# AirPi1-4.net
KiCad netlist of a schematic drawn in EAGLE
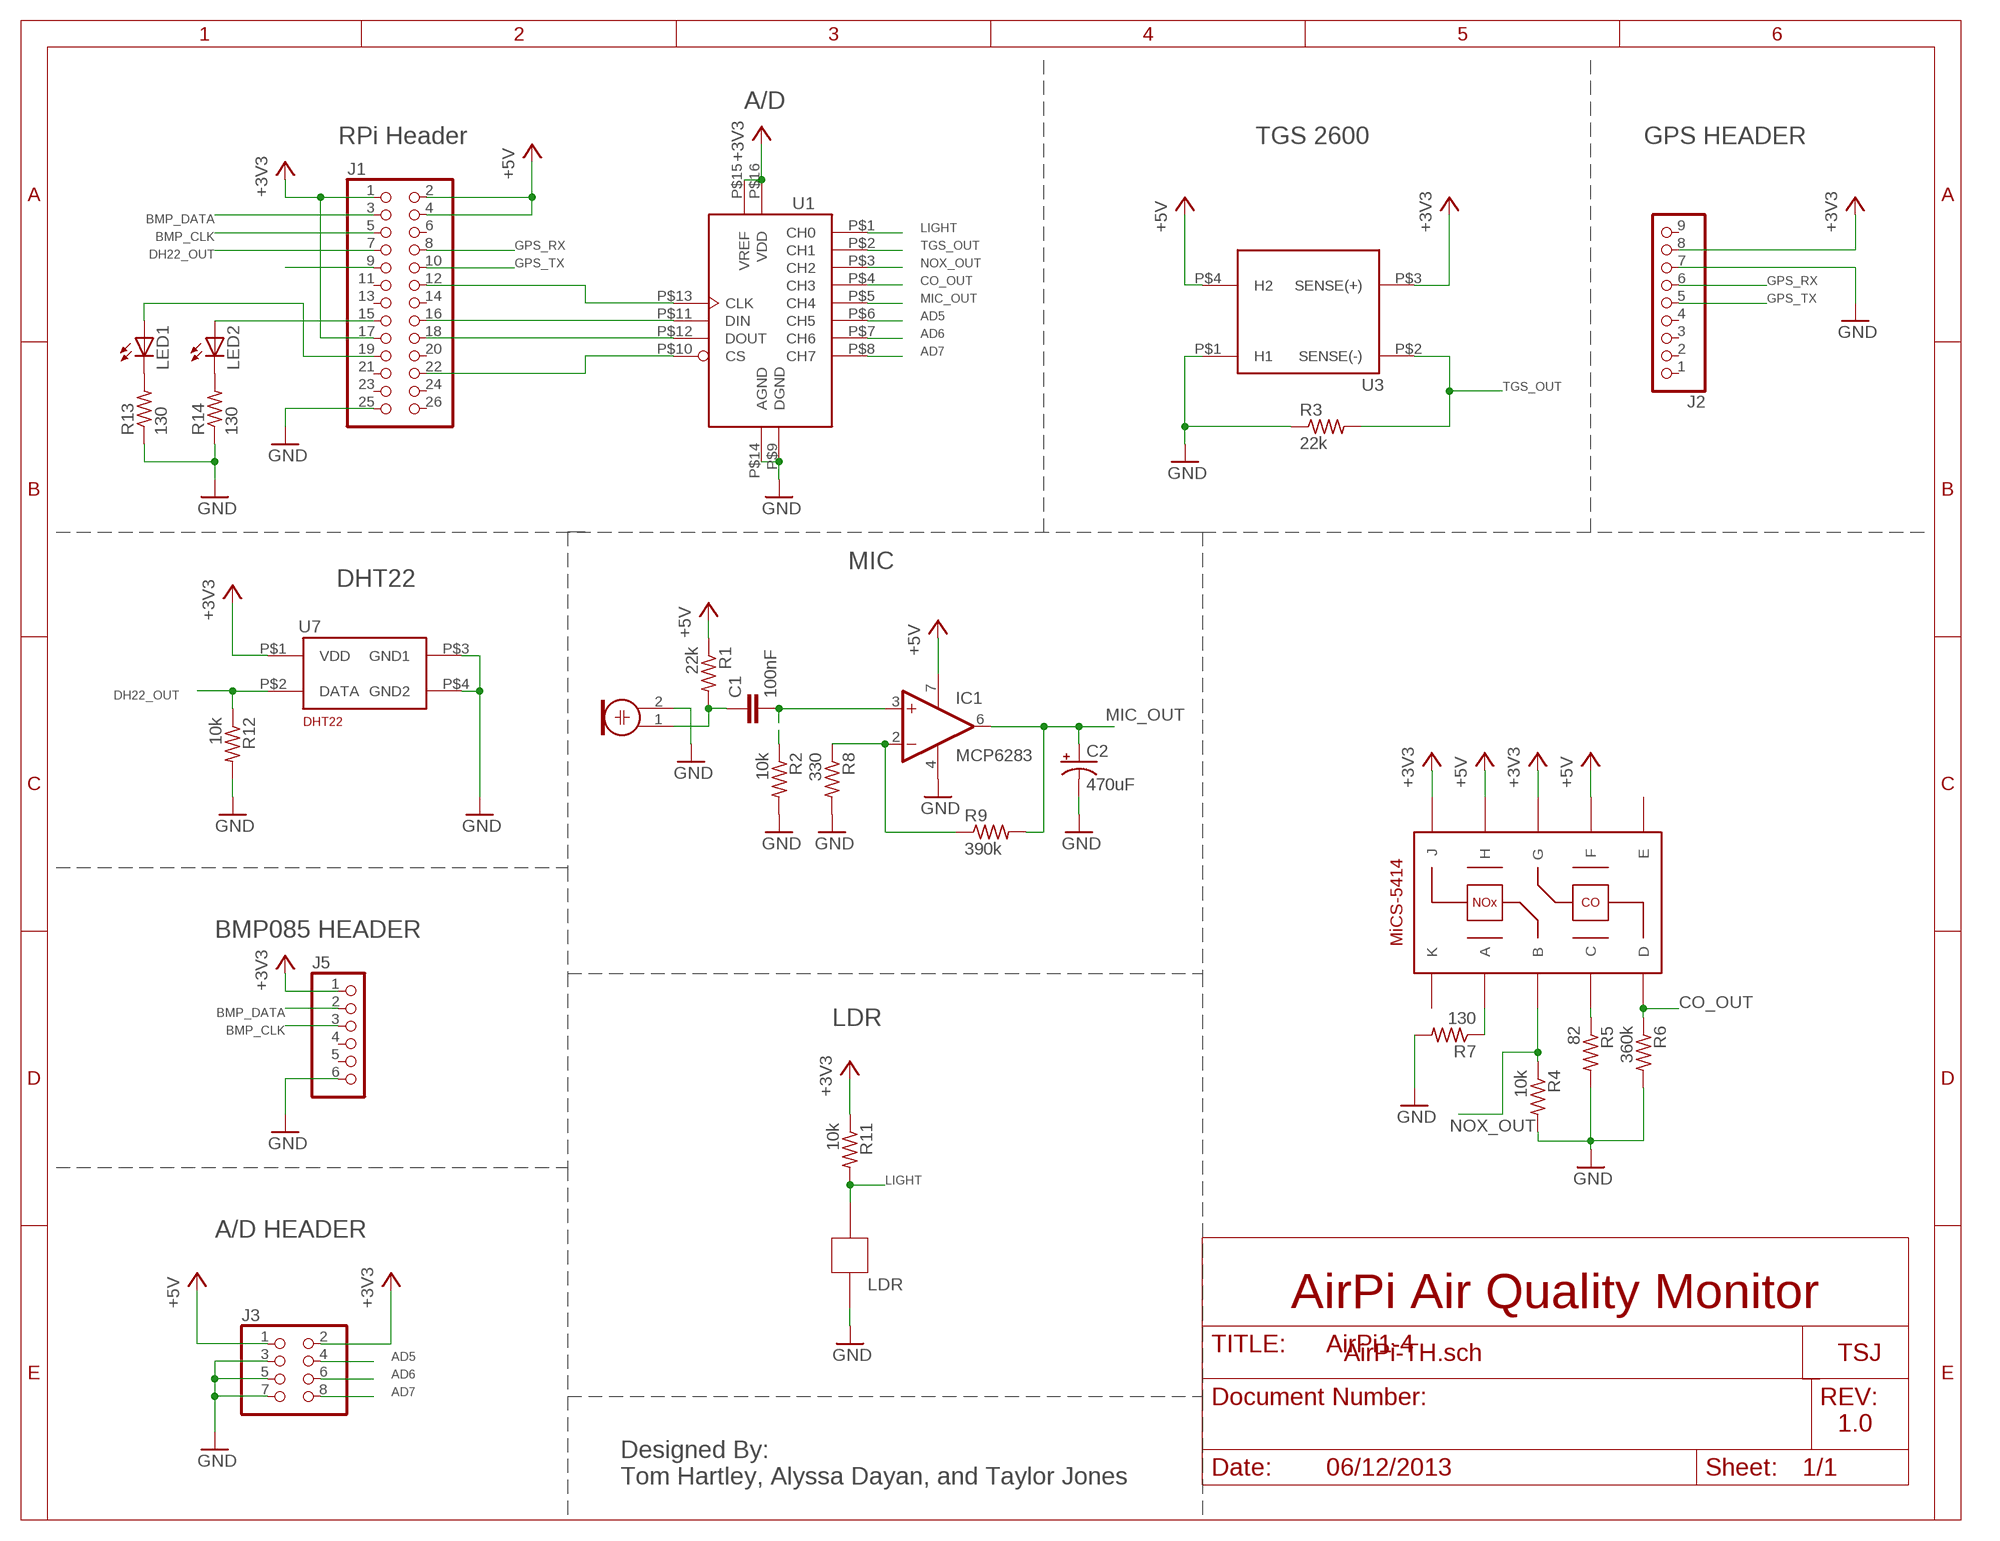
[diagram p0: schematic, sheet 1]

(export (version "E")
  (design (tool "Eeschema 10.0.6"))
  (components
    (comp (ref "C1")
      (value "100nF")
      (footprint "eagle-import:C2.5-4")
      (libsource (lib "eagle-import") (part "C2.5/4"))
    )
    (comp (ref "C2")
      (value "470uF")
      (footprint "eagle-import:E3,5-8")
      (libsource (lib "eagle-import") (part "CPOL-USE3.5-8"))
    )
    (comp (ref "IC1")
      (value "MCP6283")
      (footprint "eagle-import:DIL08")
      (libsource (lib "eagle-import") (part "OPAP344"))
    )
    (comp (ref "IC2")
      (value "MCP3008")
      (footprint "eagle-import:DIL16")
      (libsource (lib "eagle-import") (part "MCP30081"))
    )
    (comp (ref "J1")
      (value "PINHD-2X13")
      (footprint "eagle-import:2X13")
      (libsource (lib "eagle-import") (part "PINHD-2X13"))
    )
    (comp (ref "J2")
      (value "PINHD-1X9")
      (footprint "eagle-import:1X09-BIG")
      (libsource (lib "eagle-import") (part "PINHD-1X9"))
    )
    (comp (ref "J3")
      (value "PINHD-2X4")
      (footprint "eagle-import:2X04")
      (libsource (lib "eagle-import") (part "PINHD-2X4"))
    )
    (comp (ref "J5")
      (value "PINHD-1X6")
      (footprint "eagle-import:1X06")
      (libsource (lib "eagle-import") (part "PINHD-1X6"))
    )
    (comp (ref "LDR1")
      (value "LDR")
      (footprint "eagle-import:LED5MM")
      (libsource (lib "eagle-import") (part "LDR"))
    )
    (comp (ref "LED1")
      (value "LED3MM")
      (footprint "eagle-import:LED3MM")
      (libsource (lib "eagle-import") (part "LED3MM"))
    )
    (comp (ref "LED2")
      (value "LED3MM")
      (footprint "eagle-import:LED3MM")
      (libsource (lib "eagle-import") (part "LED3MM"))
    )
    (comp (ref "M1")
      (value "MIC")
      (footprint "eagle-import:WM-62PC_62PK")
      (libsource (lib "eagle-import") (part "ELECTRET_MICROPHON-WM-62PC/62PK"))
    )
    (comp (ref "MICS")
      (value "MICS-4514")
      (footprint "eagle-import:MICS-4514")
      (libsource (lib "eagle-import") (part "MICS-4514"))
    )
    (comp (ref "R1")
      (value "22k")
      (footprint "eagle-import:0207_10")
      (libsource (lib "eagle-import") (part "R-US_0207/10"))
    )
    (comp (ref "R2")
      (value "10k")
      (footprint "eagle-import:0207_10")
      (libsource (lib "eagle-import") (part "R-US_0207/10"))
    )
    (comp (ref "R3")
      (value "22k")
      (footprint "eagle-import:0207_10")
      (libsource (lib "eagle-import") (part "R-US_0207/10"))
    )
    (comp (ref "R4")
      (value "10k")
      (footprint "eagle-import:0207_10")
      (libsource (lib "eagle-import") (part "R-US_0207/10"))
    )
    (comp (ref "R5")
      (value "82")
      (footprint "eagle-import:0207_10")
      (libsource (lib "eagle-import") (part "R-US_0207/10"))
    )
    (comp (ref "R6")
      (value "360k")
      (footprint "eagle-import:0207_10")
      (libsource (lib "eagle-import") (part "R-US_0207/10"))
    )
    (comp (ref "R7")
      (value "130")
      (footprint "eagle-import:0207_10")
      (libsource (lib "eagle-import") (part "R-US_0207/10"))
    )
    (comp (ref "R8")
      (value "330")
      (footprint "eagle-import:0207_10")
      (libsource (lib "eagle-import") (part "R-US_0207/10"))
    )
    (comp (ref "R9")
      (value "390k")
      (footprint "eagle-import:0207_10")
      (libsource (lib "eagle-import") (part "R-US_0207/10"))
    )
    (comp (ref "R11")
      (value "10k")
      (footprint "eagle-import:0207_10")
      (libsource (lib "eagle-import") (part "R-US_0207/10"))
    )
    (comp (ref "R12")
      (value "10k")
      (footprint "eagle-import:0207_10")
      (libsource (lib "eagle-import") (part "R-US_0207/10"))
    )
    (comp (ref "R13")
      (value "130")
      (footprint "eagle-import:0207_10")
      (libsource (lib "eagle-import") (part "R-US_0207/10"))
    )
    (comp (ref "R14")
      (value "130")
      (footprint "eagle-import:0207_10")
      (libsource (lib "eagle-import") (part "R-US_0207/10"))
    )
    (comp (ref "U3")
      (value "TGS2600")
      (footprint "eagle-import:TGS2600")
      (libsource (lib "eagle-import") (part "TGS2600"))
    )
    (comp (ref "U7")
      (value "DHT22")
      (footprint "eagle-import:DHT22")
      (libsource (lib "eagle-import") (part "DHT22"))
    )
  )
  (nets
    (net (code "1") (name "+3V3") (class "Default")
      (node (ref "IC2") (pin "P$15") (pinfunction "VREF_P$15") (pintype "power_in"))
      (node (ref "IC2") (pin "P$16") (pinfunction "VDD_P$16") (pintype "power_in"))
      (node (ref "J1") (pin "1") (pinfunction "1_1") (pintype "passive"))
      (node (ref "J1") (pin "17") (pinfunction "17_17") (pintype "passive"))
      (node (ref "J2") (pin "8") (pinfunction "8_8") (pintype "passive"))
      (node (ref "J3") (pin "2") (pinfunction "2_2") (pintype "passive"))
      (node (ref "J5") (pin "1") (pinfunction "1_1") (pintype "passive"))
      (node (ref "MICS") (pin "G") (pinfunction "G_G") (pintype "bidirectional"))
      (node (ref "MICS") (pin "J") (pinfunction "J_J") (pintype "bidirectional"))
      (node (ref "R11") (pin "1") (pinfunction "1_1") (pintype "passive"))
      (node (ref "U3") (pin "P$3") (pinfunction "SENSE(+)_P$3") (pintype "bidirectional"))
      (node (ref "U7") (pin "P$1") (pinfunction "VDD_P$1") (pintype "power_in"))
    )
    (net (code "2") (name "+5V") (class "Default")
      (node (ref "IC1") (pin "7") (pinfunction "V+_7") (pintype "power_in"))
      (node (ref "J1") (pin "2") (pinfunction "2_2") (pintype "passive"))
      (node (ref "J1") (pin "4") (pinfunction "4_4") (pintype "passive"))
      (node (ref "J3") (pin "1") (pinfunction "1_1") (pintype "passive"))
      (node (ref "MICS") (pin "F") (pinfunction "F_F") (pintype "bidirectional"))
      (node (ref "MICS") (pin "H") (pinfunction "H_H") (pintype "bidirectional"))
      (node (ref "R1") (pin "1") (pinfunction "1_1") (pintype "passive"))
      (node (ref "U3") (pin "P$4") (pinfunction "H2_P$4") (pintype "power_in"))
    )
    (net (code "3") (name "/AD5") (class "Default")
      (node (ref "IC2") (pin "P$6") (pinfunction "CH5_P$6") (pintype "input"))
      (node (ref "J3") (pin "4") (pinfunction "4_4") (pintype "passive"))
    )
    (net (code "4") (name "/AD6") (class "Default")
      (node (ref "IC2") (pin "P$7") (pinfunction "CH6_P$7") (pintype "input"))
      (node (ref "J3") (pin "6") (pinfunction "6_6") (pintype "passive"))
    )
    (net (code "5") (name "/AD7") (class "Default")
      (node (ref "IC2") (pin "P$8") (pinfunction "CH7_P$8") (pintype "input"))
      (node (ref "J3") (pin "8") (pinfunction "8_8") (pintype "passive"))
    )
    (net (code "6") (name "/BMP_CLK") (class "Default")
      (node (ref "J1") (pin "5") (pinfunction "5_5") (pintype "passive"))
      (node (ref "J5") (pin "3") (pinfunction "3_3") (pintype "passive"))
    )
    (net (code "7") (name "/BMP_DATA") (class "Default")
      (node (ref "J1") (pin "3") (pinfunction "3_3") (pintype "passive"))
      (node (ref "J5") (pin "2") (pinfunction "2_2") (pintype "passive"))
    )
    (net (code "8") (name "/CO_OUT") (class "Default")
      (node (ref "IC2") (pin "P$4") (pinfunction "CH3_P$4") (pintype "input"))
      (node (ref "MICS") (pin "D") (pinfunction "D_D") (pintype "bidirectional"))
      (node (ref "R6") (pin "1") (pinfunction "1_1") (pintype "passive"))
    )
    (net (code "9") (name "/DH22_OUT") (class "Default")
      (node (ref "J1") (pin "7") (pinfunction "7_7") (pintype "passive"))
      (node (ref "R12") (pin "1") (pinfunction "1_1") (pintype "passive"))
      (node (ref "U7") (pin "P$2") (pinfunction "DATA_P$2") (pintype "bidirectional"))
    )
    (net (code "10") (name "/GPS_RX") (class "Default")
      (node (ref "J1") (pin "8") (pinfunction "8_8") (pintype "passive"))
      (node (ref "J2") (pin "6") (pinfunction "6_6") (pintype "passive"))
    )
    (net (code "11") (name "/GPS_TX") (class "Default")
      (node (ref "J1") (pin "10") (pinfunction "10_10") (pintype "passive"))
      (node (ref "J2") (pin "5") (pinfunction "5_5") (pintype "passive"))
    )
    (net (code "12") (name "/LIGHT") (class "Default")
      (node (ref "IC2") (pin "P$1") (pinfunction "CH0_P$1") (pintype "input"))
      (node (ref "LDR1") (pin "A") (pinfunction "P$1_A") (pintype "bidirectional"))
      (node (ref "R11") (pin "2") (pinfunction "2_2") (pintype "passive"))
    )
    (net (code "13") (name "/MIC_OUT") (class "Default")
      (node (ref "C2") (pin "+") (pinfunction "+_+") (pintype "passive"))
      (node (ref "IC1") (pin "6") (pinfunction "OUT_6") (pintype "output"))
      (node (ref "IC2") (pin "P$5") (pinfunction "CH4_P$5") (pintype "input"))
      (node (ref "R9") (pin "2") (pinfunction "2_2") (pintype "passive"))
    )
    (net (code "14") (name "/NOX_OUT") (class "Default")
      (node (ref "IC2") (pin "P$3") (pinfunction "CH2_P$3") (pintype "input"))
      (node (ref "MICS") (pin "B") (pinfunction "B_B") (pintype "bidirectional"))
      (node (ref "R4") (pin "1") (pinfunction "1_1") (pintype "passive"))
    )
    (net (code "15") (name "/TGS_OUT") (class "Default")
      (node (ref "IC2") (pin "P$2") (pinfunction "CH1_P$2") (pintype "input"))
      (node (ref "R3") (pin "2") (pinfunction "2_2") (pintype "passive"))
      (node (ref "U3") (pin "P$2") (pinfunction "SENSE(-)_P$2") (pintype "bidirectional"))
    )
    (net (code "16") (name "GND") (class "Default")
      (node (ref "C2") (pin "-") (pinfunction "-_-") (pintype "passive"))
      (node (ref "IC1") (pin "4") (pinfunction "V-_4") (pintype "power_in"))
      (node (ref "IC2") (pin "P$14") (pinfunction "AGND_P$14") (pintype "power_in"))
      (node (ref "IC2") (pin "P$9") (pinfunction "DGND_P$9") (pintype "power_in"))
      (node (ref "J1") (pin "25") (pinfunction "25_25") (pintype "passive"))
      (node (ref "J2") (pin "7") (pinfunction "7_7") (pintype "passive"))
      (node (ref "J3") (pin "3") (pinfunction "3_3") (pintype "passive"))
      (node (ref "J3") (pin "5") (pinfunction "5_5") (pintype "passive"))
      (node (ref "J3") (pin "7") (pinfunction "7_7") (pintype "passive"))
      (node (ref "J5") (pin "6") (pinfunction "6_6") (pintype "passive"))
      (node (ref "LDR1") (pin "K") (pinfunction "P$2_K") (pintype "bidirectional"))
      (node (ref "M1") (pin "2") (pinfunction "2_2") (pintype "passive"))
      (node (ref "R12") (pin "2") (pinfunction "2_2") (pintype "passive"))
      (node (ref "R13") (pin "1") (pinfunction "1_1") (pintype "passive"))
      (node (ref "R14") (pin "1") (pinfunction "1_1") (pintype "passive"))
      (node (ref "R2") (pin "2") (pinfunction "2_2") (pintype "passive"))
      (node (ref "R3") (pin "1") (pinfunction "1_1") (pintype "passive"))
      (node (ref "R4") (pin "2") (pinfunction "2_2") (pintype "passive"))
      (node (ref "R5") (pin "2") (pinfunction "2_2") (pintype "passive"))
      (node (ref "R6") (pin "2") (pinfunction "2_2") (pintype "passive"))
      (node (ref "R7") (pin "2") (pinfunction "2_2") (pintype "passive"))
      (node (ref "R8") (pin "2") (pinfunction "2_2") (pintype "passive"))
      (node (ref "U3") (pin "P$1") (pinfunction "H1_P$1") (pintype "power_in"))
      (node (ref "U7") (pin "P$3") (pinfunction "GND1_P$3") (pintype "power_in"))
      (node (ref "U7") (pin "P$4") (pinfunction "GND2_P$4") (pintype "bidirectional"))
    )
    (net (code "17") (name "Net-(C1-Pad1)") (class "Default")
      (node (ref "C1") (pin "1") (pinfunction "1_1") (pintype "passive"))
      (node (ref "M1") (pin "1") (pinfunction "1_1") (pintype "passive"))
      (node (ref "R1") (pin "2") (pinfunction "2_2") (pintype "passive"))
    )
    (net (code "18") (name "Net-(IC1-+IN)") (class "Default")
      (node (ref "C1") (pin "2") (pinfunction "2_2") (pintype "passive"))
      (node (ref "IC1") (pin "3") (pinfunction "+IN_3") (pintype "input"))
      (node (ref "R2") (pin "1") (pinfunction "1_1") (pintype "passive"))
    )
    (net (code "19") (name "Net-(IC1--IN)") (class "Default")
      (node (ref "IC1") (pin "2") (pinfunction "-IN_2") (pintype "input"))
      (node (ref "R8") (pin "1") (pinfunction "1_1") (pintype "passive"))
      (node (ref "R9") (pin "1") (pinfunction "1_1") (pintype "passive"))
    )
    (net (code "20") (name "Net-(IC2-CLK)") (class "Default")
      (node (ref "IC2") (pin "P$13") (pinfunction "CLK_P$13") (pintype "input"))
      (node (ref "J1") (pin "12") (pinfunction "12_12") (pintype "passive"))
    )
    (net (code "21") (name "Net-(IC2-CS)") (class "Default")
      (node (ref "IC2") (pin "P$10") (pinfunction "CS_P$10") (pintype "input"))
      (node (ref "J1") (pin "22") (pinfunction "22_22") (pintype "passive"))
    )
    (net (code "22") (name "Net-(IC2-DIN)") (class "Default")
      (node (ref "IC2") (pin "P$11") (pinfunction "DIN_P$11") (pintype "input"))
      (node (ref "J1") (pin "16") (pinfunction "16_16") (pintype "passive"))
    )
    (net (code "23") (name "Net-(IC2-DOUT)") (class "Default")
      (node (ref "IC2") (pin "P$12") (pinfunction "DOUT_P$12") (pintype "output"))
      (node (ref "J1") (pin "18") (pinfunction "18_18") (pintype "passive"))
    )
    (net (code "24") (name "Net-(J1-Pad15)") (class "Default")
      (node (ref "J1") (pin "15") (pinfunction "15_15") (pintype "passive"))
      (node (ref "LED2") (pin "A") (pinfunction "A_A") (pintype "passive"))
    )
    (net (code "25") (name "Net-(J1-Pad19)") (class "Default")
      (node (ref "J1") (pin "19") (pinfunction "19_19") (pintype "passive"))
      (node (ref "LED1") (pin "A") (pinfunction "A_A") (pintype "passive"))
    )
    (net (code "26") (name "Net-(LED1-C)") (class "Default")
      (node (ref "LED1") (pin "K") (pinfunction "C_K") (pintype "passive"))
      (node (ref "R13") (pin "2") (pinfunction "2_2") (pintype "passive"))
    )
    (net (code "27") (name "Net-(LED2-C)") (class "Default")
      (node (ref "LED2") (pin "K") (pinfunction "C_K") (pintype "passive"))
      (node (ref "R14") (pin "2") (pinfunction "2_2") (pintype "passive"))
    )
    (net (code "28") (name "Net-(MICS-PadA)") (class "Default")
      (node (ref "MICS") (pin "A") (pinfunction "A_A") (pintype "bidirectional"))
      (node (ref "R7") (pin "1") (pinfunction "1_1") (pintype "passive"))
    )
    (net (code "29") (name "Net-(MICS-PadC)") (class "Default")
      (node (ref "MICS") (pin "C") (pinfunction "C_C") (pintype "bidirectional"))
      (node (ref "R5") (pin "1") (pinfunction "1_1") (pintype "passive"))
    )
    (net (code "30") (name "unconnected-(J1-Pad6)") (class "Default")
      (node (ref "J1") (pin "6") (pinfunction "6_6") (pintype "passive"))
    )
    (net (code "31") (name "unconnected-(J1-Pad9)") (class "Default")
      (node (ref "J1") (pin "9") (pinfunction "9_9") (pintype "passive"))
    )
    (net (code "32") (name "unconnected-(J1-Pad11)") (class "Default")
      (node (ref "J1") (pin "11") (pinfunction "11_11") (pintype "passive"))
    )
    (net (code "33") (name "unconnected-(J1-Pad13)") (class "Default")
      (node (ref "J1") (pin "13") (pinfunction "13_13") (pintype "passive"))
    )
    (net (code "34") (name "unconnected-(J1-Pad14)") (class "Default")
      (node (ref "J1") (pin "14") (pinfunction "14_14") (pintype "passive"))
    )
    (net (code "35") (name "unconnected-(J1-Pad20)") (class "Default")
      (node (ref "J1") (pin "20") (pinfunction "20_20") (pintype "passive"))
    )
    (net (code "36") (name "unconnected-(J1-Pad21)") (class "Default")
      (node (ref "J1") (pin "21") (pinfunction "21_21") (pintype "passive"))
    )
    (net (code "37") (name "unconnected-(J1-Pad23)") (class "Default")
      (node (ref "J1") (pin "23") (pinfunction "23_23") (pintype "passive"))
    )
    (net (code "38") (name "unconnected-(J1-Pad24)") (class "Default")
      (node (ref "J1") (pin "24") (pinfunction "24_24") (pintype "passive"))
    )
    (net (code "39") (name "unconnected-(J1-Pad26)") (class "Default")
      (node (ref "J1") (pin "26") (pinfunction "26_26") (pintype "passive"))
    )
    (net (code "40") (name "unconnected-(J2-Pad1)") (class "Default")
      (node (ref "J2") (pin "1") (pinfunction "1_1") (pintype "passive"))
    )
    (net (code "41") (name "unconnected-(J2-Pad2)") (class "Default")
      (node (ref "J2") (pin "2") (pinfunction "2_2") (pintype "passive"))
    )
    (net (code "42") (name "unconnected-(J2-Pad3)") (class "Default")
      (node (ref "J2") (pin "3") (pinfunction "3_3") (pintype "passive"))
    )
    (net (code "43") (name "unconnected-(J2-Pad4)") (class "Default")
      (node (ref "J2") (pin "4") (pinfunction "4_4") (pintype "passive"))
    )
    (net (code "44") (name "unconnected-(J2-Pad9)") (class "Default")
      (node (ref "J2") (pin "9") (pinfunction "9_9") (pintype "passive"))
    )
    (net (code "45") (name "unconnected-(J5-Pad4)") (class "Default")
      (node (ref "J5") (pin "4") (pinfunction "4_4") (pintype "passive"))
    )
    (net (code "46") (name "unconnected-(J5-Pad5)") (class "Default")
      (node (ref "J5") (pin "5") (pinfunction "5_5") (pintype "passive"))
    )
    (net (code "47") (name "unconnected-(MICS-PadE)") (class "Default")
      (node (ref "MICS") (pin "E") (pinfunction "E_E") (pintype "bidirectional"))
    )
    (net (code "48") (name "unconnected-(MICS-PadK)") (class "Default")
      (node (ref "MICS") (pin "K") (pinfunction "K_K") (pintype "bidirectional"))
    )
  )
)
